# incubator.net
KiCad netlist of a schematic drawn in EAGLE
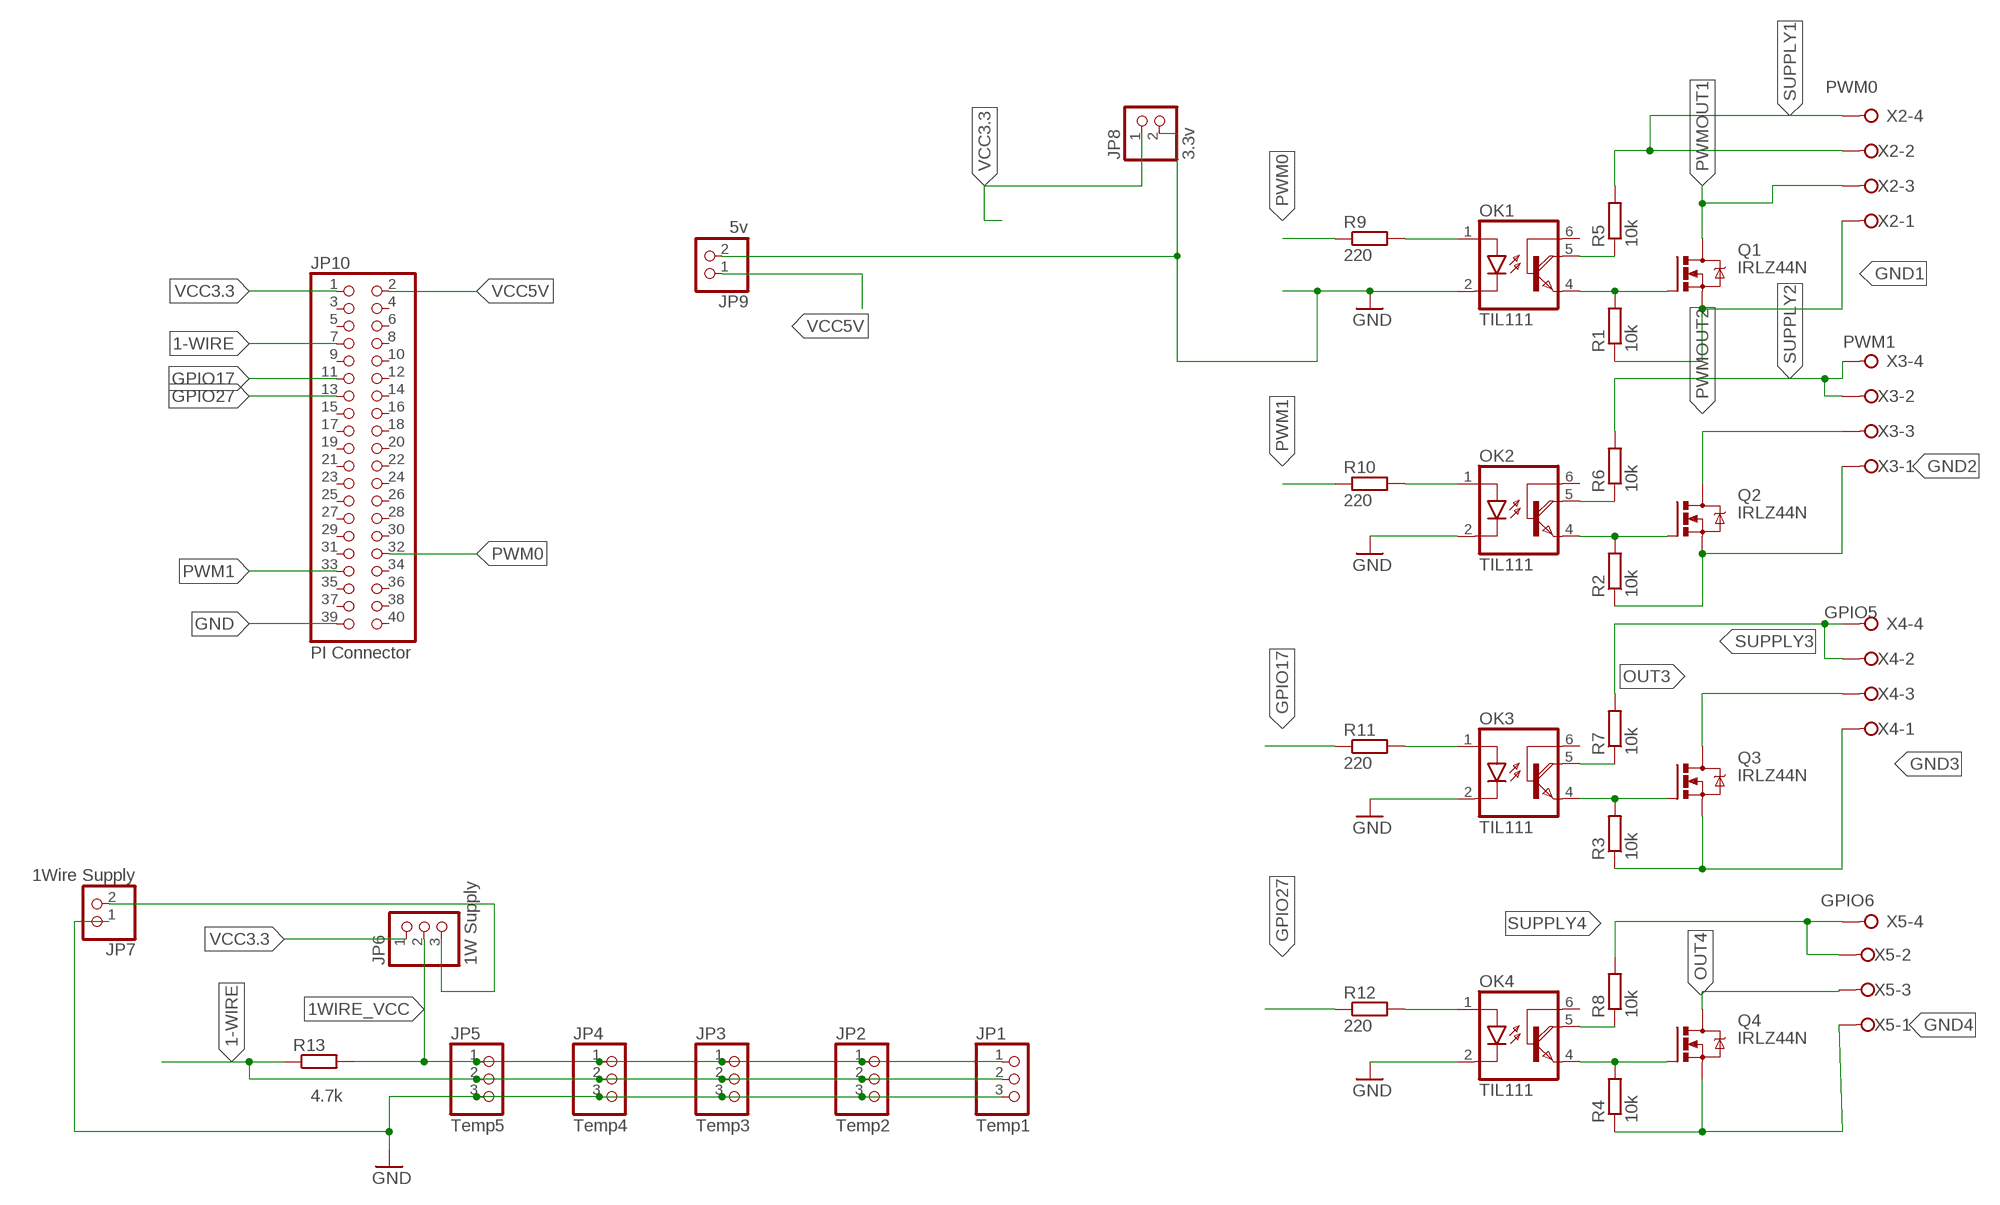
[diagram p0: schematic, sheet 1]

(export (version "E")
  (design (tool "Eeschema 10.0.6"))
  (components
    (comp (ref "JP1")
      (value "Temp1")
      (footprint "eagle-import:1X03")
      (libsource (lib "eagle-import") (part "PINHD-1X3"))
    )
    (comp (ref "JP2")
      (value "Temp2")
      (footprint "eagle-import:1X03")
      (libsource (lib "eagle-import") (part "PINHD-1X3"))
    )
    (comp (ref "JP3")
      (value "Temp3")
      (footprint "eagle-import:1X03")
      (libsource (lib "eagle-import") (part "PINHD-1X3"))
    )
    (comp (ref "JP4")
      (value "Temp4")
      (footprint "eagle-import:1X03")
      (libsource (lib "eagle-import") (part "PINHD-1X3"))
    )
    (comp (ref "JP5")
      (value "Temp5")
      (footprint "eagle-import:1X03")
      (libsource (lib "eagle-import") (part "PINHD-1X3"))
    )
    (comp (ref "JP6")
      (value "1W Supply")
      (footprint "eagle-import:1X03")
      (libsource (lib "eagle-import") (part "PINHD-1X3"))
    )
    (comp (ref "JP7")
      (value "1Wire Supply")
      (footprint "eagle-import:1X02")
      (libsource (lib "eagle-import") (part "PINHD-1X2"))
    )
    (comp (ref "JP8")
      (value "3.3v")
      (footprint "eagle-import:1X02")
      (libsource (lib "eagle-import") (part "PINHD-1X2"))
    )
    (comp (ref "JP9")
      (value "5v")
      (footprint "eagle-import:1X02")
      (libsource (lib "eagle-import") (part "PINHD-1X2"))
    )
    (comp (ref "JP10")
      (value "PI Connector")
      (footprint "eagle-import:2X20")
      (libsource (lib "eagle-import") (part "PINHD-2X20"))
    )
    (comp (ref "OK1")
      (value "TIL111")
      (footprint "eagle-import:DIL06")
      (fields (field (name "MF") "VISHAY/TELEFUNKEN") (field (name "MPN") "4N33"))
      (libsource (lib "eagle-import") (part "4N33"))
    )
    (comp (ref "OK2")
      (value "TIL111")
      (footprint "eagle-import:DIL06")
      (fields (field (name "MF") "VISHAY/TELEFUNKEN") (field (name "MPN") "4N33"))
      (libsource (lib "eagle-import") (part "4N33"))
    )
    (comp (ref "OK3")
      (value "TIL111")
      (footprint "eagle-import:DIL06")
      (fields (field (name "MF") "VISHAY/TELEFUNKEN") (field (name "MPN") "4N33"))
      (libsource (lib "eagle-import") (part "4N33"))
    )
    (comp (ref "OK4")
      (value "TIL111")
      (footprint "eagle-import:DIL06")
      (fields (field (name "MF") "VISHAY/TELEFUNKEN") (field (name "MPN") "4N33"))
      (libsource (lib "eagle-import") (part "4N33"))
    )
    (comp (ref "Q1")
      (value "IRLZ44N")
      (footprint "eagle-import:TO220BH")
      (libsource (lib "eagle-import") (part "IRLZ44Z"))
    )
    (comp (ref "Q2")
      (value "IRLZ44N")
      (footprint "eagle-import:TO220BH")
      (libsource (lib "eagle-import") (part "IRLZ44Z"))
    )
    (comp (ref "Q3")
      (value "IRLZ44N")
      (footprint "eagle-import:TO220BH")
      (libsource (lib "eagle-import") (part "IRLZ44Z"))
    )
    (comp (ref "Q4")
      (value "IRLZ44N")
      (footprint "eagle-import:TO220BH")
      (libsource (lib "eagle-import") (part "IRLZ44Z"))
    )
    (comp (ref "R1")
      (value "10k")
      (footprint "eagle-import:0207_7")
      (libsource (lib "eagle-import") (part "R-EU_0207/7"))
    )
    (comp (ref "R2")
      (value "10k")
      (footprint "eagle-import:0207_7")
      (libsource (lib "eagle-import") (part "R-EU_0207/7"))
    )
    (comp (ref "R3")
      (value "10k")
      (footprint "eagle-import:0207_7")
      (libsource (lib "eagle-import") (part "R-EU_0207/7"))
    )
    (comp (ref "R4")
      (value "10k")
      (footprint "eagle-import:0207_7")
      (libsource (lib "eagle-import") (part "R-EU_0207/7"))
    )
    (comp (ref "R5")
      (value "10k")
      (footprint "eagle-import:0207_7")
      (libsource (lib "eagle-import") (part "R-EU_0207/7"))
    )
    (comp (ref "R6")
      (value "10k")
      (footprint "eagle-import:0207_7")
      (libsource (lib "eagle-import") (part "R-EU_0207/7"))
    )
    (comp (ref "R7")
      (value "10k")
      (footprint "eagle-import:0207_7")
      (libsource (lib "eagle-import") (part "R-EU_0207/7"))
    )
    (comp (ref "R8")
      (value "10k")
      (footprint "eagle-import:0207_7")
      (libsource (lib "eagle-import") (part "R-EU_0207/7"))
    )
    (comp (ref "R9")
      (value "220")
      (footprint "eagle-import:0207_7")
      (libsource (lib "eagle-import") (part "R-EU_0207/7"))
    )
    (comp (ref "R10")
      (value "220")
      (footprint "eagle-import:0207_7")
      (libsource (lib "eagle-import") (part "R-EU_0207/7"))
    )
    (comp (ref "R11")
      (value "220")
      (footprint "eagle-import:0207_7")
      (libsource (lib "eagle-import") (part "R-EU_0207/7"))
    )
    (comp (ref "R12")
      (value "220")
      (footprint "eagle-import:0207_7")
      (libsource (lib "eagle-import") (part "R-EU_0207/7"))
    )
    (comp (ref "R13")
      (value "4.7k")
      (footprint "eagle-import:0207_7")
      (libsource (lib "eagle-import") (part "R-EU_0207/7"))
    )
    (comp (ref "X2")
      (value "PWM0")
      (footprint "eagle-import:W237-4P")
      (libsource (lib "eagle-import") (part "W237-04P"))
    )
    (comp (ref "X3")
      (value "PWM1")
      (footprint "eagle-import:W237-4P")
      (libsource (lib "eagle-import") (part "W237-04P"))
    )
    (comp (ref "X4")
      (value "GPIO5")
      (footprint "eagle-import:W237-4P")
      (libsource (lib "eagle-import") (part "W237-04P"))
    )
    (comp (ref "X5")
      (value "GPIO6")
      (footprint "eagle-import:W237-4P")
      (libsource (lib "eagle-import") (part "W237-04P"))
    )
  )
  (nets
    (net (code "1") (name "1-WIRE") (class "Default")
      (node (ref "JP1") (pin "2") (pinfunction "2_2") (pintype "passive"))
      (node (ref "JP10") (pin "7") (pinfunction "7_7") (pintype "passive"))
      (node (ref "JP2") (pin "2") (pinfunction "2_2") (pintype "passive"))
      (node (ref "JP3") (pin "2") (pinfunction "2_2") (pintype "passive"))
      (node (ref "JP4") (pin "2") (pinfunction "2_2") (pintype "passive"))
      (node (ref "JP5") (pin "2") (pinfunction "2_2") (pintype "passive"))
      (node (ref "R13") (pin "1") (pinfunction "1_1") (pintype "passive"))
    )
    (net (code "2") (name "1WIRE_VCC") (class "Default")
      (node (ref "JP1") (pin "1") (pinfunction "1_1") (pintype "passive"))
      (node (ref "JP2") (pin "1") (pinfunction "1_1") (pintype "passive"))
      (node (ref "JP3") (pin "1") (pinfunction "1_1") (pintype "passive"))
      (node (ref "JP4") (pin "1") (pinfunction "1_1") (pintype "passive"))
      (node (ref "JP5") (pin "1") (pinfunction "1_1") (pintype "passive"))
      (node (ref "JP6") (pin "2") (pinfunction "2_2") (pintype "passive"))
      (node (ref "R13") (pin "2") (pinfunction "2_2") (pintype "passive"))
    )
    (net (code "3") (name "GND") (class "Default")
      (node (ref "JP1") (pin "3") (pinfunction "3_3") (pintype "passive"))
      (node (ref "JP10") (pin "39") (pinfunction "39_39") (pintype "passive"))
      (node (ref "JP2") (pin "3") (pinfunction "3_3") (pintype "passive"))
      (node (ref "JP3") (pin "3") (pinfunction "3_3") (pintype "passive"))
      (node (ref "JP4") (pin "3") (pinfunction "3_3") (pintype "passive"))
      (node (ref "JP5") (pin "3") (pinfunction "3_3") (pintype "passive"))
      (node (ref "JP7") (pin "1") (pinfunction "1_1") (pintype "passive"))
      (node (ref "JP8") (pin "2") (pinfunction "2_2") (pintype "passive"))
      (node (ref "JP9") (pin "2") (pinfunction "2_2") (pintype "passive"))
      (node (ref "OK1") (pin "2") (pinfunction "C_2") (pintype "passive"))
      (node (ref "OK2") (pin "2") (pinfunction "C_2") (pintype "passive"))
      (node (ref "OK3") (pin "2") (pinfunction "C_2") (pintype "passive"))
      (node (ref "OK4") (pin "2") (pinfunction "C_2") (pintype "passive"))
    )
    (net (code "4") (name "GND1") (class "Default")
      (node (ref "Q1") (pin "S") (pinfunction "S_S") (pintype "passive"))
      (node (ref "R1") (pin "1") (pinfunction "1_1") (pintype "passive"))
      (node (ref "X2") (pin "1") (pinfunction "KL_1") (pintype "passive"))
    )
    (net (code "5") (name "GND2") (class "Default")
      (node (ref "Q2") (pin "S") (pinfunction "S_S") (pintype "passive"))
      (node (ref "R2") (pin "1") (pinfunction "1_1") (pintype "passive"))
      (node (ref "X3") (pin "1") (pinfunction "KL_1") (pintype "passive"))
    )
    (net (code "6") (name "GND3") (class "Default")
      (node (ref "Q3") (pin "S") (pinfunction "S_S") (pintype "passive"))
      (node (ref "R3") (pin "1") (pinfunction "1_1") (pintype "passive"))
      (node (ref "X4") (pin "1") (pinfunction "KL_1") (pintype "passive"))
    )
    (net (code "7") (name "GND4") (class "Default")
      (node (ref "Q4") (pin "S") (pinfunction "S_S") (pintype "passive"))
      (node (ref "R4") (pin "1") (pinfunction "1_1") (pintype "passive"))
      (node (ref "X5") (pin "1") (pinfunction "KL_1") (pintype "passive"))
    )
    (net (code "8") (name "GPIO17") (class "Default")
      (node (ref "JP10") (pin "11") (pinfunction "11_11") (pintype "passive"))
      (node (ref "R11") (pin "1") (pinfunction "1_1") (pintype "passive"))
    )
    (net (code "9") (name "GPIO27") (class "Default")
      (node (ref "JP10") (pin "13") (pinfunction "13_13") (pintype "passive"))
      (node (ref "R12") (pin "1") (pinfunction "1_1") (pintype "passive"))
    )
    (net (code "10") (name "Net-(JP6-Pad3)") (class "Default")
      (node (ref "JP6") (pin "3") (pinfunction "3_3") (pintype "passive"))
      (node (ref "JP7") (pin "2") (pinfunction "2_2") (pintype "passive"))
    )
    (net (code "11") (name "Net-(OK1-A)") (class "Default")
      (node (ref "OK1") (pin "1") (pinfunction "A_1") (pintype "passive"))
      (node (ref "R9") (pin "2") (pinfunction "2_2") (pintype "passive"))
    )
    (net (code "12") (name "Net-(OK1-COL)") (class "Default")
      (node (ref "OK1") (pin "5") (pinfunction "COL_5") (pintype "passive"))
      (node (ref "R5") (pin "1") (pinfunction "1_1") (pintype "passive"))
    )
    (net (code "13") (name "Net-(OK1-E)") (class "Default")
      (node (ref "OK1") (pin "4") (pinfunction "E_4") (pintype "passive"))
      (node (ref "Q1") (pin "G") (pinfunction "G_G") (pintype "passive"))
      (node (ref "R1") (pin "2") (pinfunction "2_2") (pintype "passive"))
    )
    (net (code "14") (name "Net-(OK2-A)") (class "Default")
      (node (ref "OK2") (pin "1") (pinfunction "A_1") (pintype "passive"))
      (node (ref "R10") (pin "2") (pinfunction "2_2") (pintype "passive"))
    )
    (net (code "15") (name "Net-(OK2-COL)") (class "Default")
      (node (ref "OK2") (pin "5") (pinfunction "COL_5") (pintype "passive"))
      (node (ref "R6") (pin "1") (pinfunction "1_1") (pintype "passive"))
    )
    (net (code "16") (name "Net-(OK2-E)") (class "Default")
      (node (ref "OK2") (pin "4") (pinfunction "E_4") (pintype "passive"))
      (node (ref "Q2") (pin "G") (pinfunction "G_G") (pintype "passive"))
      (node (ref "R2") (pin "2") (pinfunction "2_2") (pintype "passive"))
    )
    (net (code "17") (name "Net-(OK3-A)") (class "Default")
      (node (ref "OK3") (pin "1") (pinfunction "A_1") (pintype "passive"))
      (node (ref "R11") (pin "2") (pinfunction "2_2") (pintype "passive"))
    )
    (net (code "18") (name "Net-(OK3-COL)") (class "Default")
      (node (ref "OK3") (pin "5") (pinfunction "COL_5") (pintype "passive"))
      (node (ref "R7") (pin "1") (pinfunction "1_1") (pintype "passive"))
    )
    (net (code "19") (name "Net-(OK3-E)") (class "Default")
      (node (ref "OK3") (pin "4") (pinfunction "E_4") (pintype "passive"))
      (node (ref "Q3") (pin "G") (pinfunction "G_G") (pintype "passive"))
      (node (ref "R3") (pin "2") (pinfunction "2_2") (pintype "passive"))
    )
    (net (code "20") (name "Net-(OK4-A)") (class "Default")
      (node (ref "OK4") (pin "1") (pinfunction "A_1") (pintype "passive"))
      (node (ref "R12") (pin "2") (pinfunction "2_2") (pintype "passive"))
    )
    (net (code "21") (name "Net-(OK4-COL)") (class "Default")
      (node (ref "OK4") (pin "5") (pinfunction "COL_5") (pintype "passive"))
      (node (ref "R8") (pin "1") (pinfunction "1_1") (pintype "passive"))
    )
    (net (code "22") (name "Net-(OK4-E)") (class "Default")
      (node (ref "OK4") (pin "4") (pinfunction "E_4") (pintype "passive"))
      (node (ref "Q4") (pin "G") (pinfunction "G_G") (pintype "passive"))
      (node (ref "R4") (pin "2") (pinfunction "2_2") (pintype "passive"))
    )
    (net (code "23") (name "OUT3") (class "Default")
      (node (ref "Q3") (pin "D") (pinfunction "D_D") (pintype "passive"))
      (node (ref "X4") (pin "3") (pinfunction "KL_3") (pintype "passive"))
    )
    (net (code "24") (name "OUT4") (class "Default")
      (node (ref "Q4") (pin "D") (pinfunction "D_D") (pintype "passive"))
      (node (ref "X5") (pin "3") (pinfunction "KL_3") (pintype "passive"))
    )
    (net (code "25") (name "PWM0") (class "Default")
      (node (ref "JP10") (pin "32") (pinfunction "32_32") (pintype "passive"))
      (node (ref "R9") (pin "1") (pinfunction "1_1") (pintype "passive"))
    )
    (net (code "26") (name "PWM1") (class "Default")
      (node (ref "JP10") (pin "33") (pinfunction "33_33") (pintype "passive"))
      (node (ref "R10") (pin "1") (pinfunction "1_1") (pintype "passive"))
    )
    (net (code "27") (name "PWMOUT1") (class "Default")
      (node (ref "Q1") (pin "D") (pinfunction "D_D") (pintype "passive"))
      (node (ref "X2") (pin "3") (pinfunction "KL_3") (pintype "passive"))
    )
    (net (code "28") (name "PWMOUT2") (class "Default")
      (node (ref "Q2") (pin "D") (pinfunction "D_D") (pintype "passive"))
      (node (ref "X3") (pin "3") (pinfunction "KL_3") (pintype "passive"))
    )
    (net (code "29") (name "SUPPLY1") (class "Default")
      (node (ref "R5") (pin "2") (pinfunction "2_2") (pintype "passive"))
      (node (ref "X2") (pin "2") (pinfunction "KL_2") (pintype "passive"))
      (node (ref "X2") (pin "4") (pinfunction "KL_4") (pintype "passive"))
    )
    (net (code "30") (name "SUPPLY2") (class "Default")
      (node (ref "R6") (pin "2") (pinfunction "2_2") (pintype "passive"))
      (node (ref "X3") (pin "2") (pinfunction "KL_2") (pintype "passive"))
      (node (ref "X3") (pin "4") (pinfunction "KL_4") (pintype "passive"))
    )
    (net (code "31") (name "SUPPLY3") (class "Default")
      (node (ref "R7") (pin "2") (pinfunction "2_2") (pintype "passive"))
      (node (ref "X4") (pin "2") (pinfunction "KL_2") (pintype "passive"))
      (node (ref "X4") (pin "4") (pinfunction "KL_4") (pintype "passive"))
    )
    (net (code "32") (name "SUPPLY4") (class "Default")
      (node (ref "R8") (pin "2") (pinfunction "2_2") (pintype "passive"))
      (node (ref "X5") (pin "2") (pinfunction "KL_2") (pintype "passive"))
      (node (ref "X5") (pin "4") (pinfunction "KL_4") (pintype "passive"))
    )
    (net (code "33") (name "VCC3.3") (class "Default")
      (node (ref "JP10") (pin "1") (pinfunction "1_1") (pintype "passive"))
      (node (ref "JP6") (pin "1") (pinfunction "1_1") (pintype "passive"))
      (node (ref "JP8") (pin "1") (pinfunction "1_1") (pintype "passive"))
    )
    (net (code "34") (name "VCC5V") (class "Default")
      (node (ref "JP10") (pin "2") (pinfunction "2_2") (pintype "passive"))
      (node (ref "JP9") (pin "1") (pinfunction "1_1") (pintype "passive"))
    )
    (net (code "35") (name "unconnected-(JP10-Pad3)") (class "Default")
      (node (ref "JP10") (pin "3") (pinfunction "3_3") (pintype "passive"))
    )
    (net (code "36") (name "unconnected-(JP10-Pad4)") (class "Default")
      (node (ref "JP10") (pin "4") (pinfunction "4_4") (pintype "passive"))
    )
    (net (code "37") (name "unconnected-(JP10-Pad5)") (class "Default")
      (node (ref "JP10") (pin "5") (pinfunction "5_5") (pintype "passive"))
    )
    (net (code "38") (name "unconnected-(JP10-Pad6)") (class "Default")
      (node (ref "JP10") (pin "6") (pinfunction "6_6") (pintype "passive"))
    )
    (net (code "39") (name "unconnected-(JP10-Pad8)") (class "Default")
      (node (ref "JP10") (pin "8") (pinfunction "8_8") (pintype "passive"))
    )
    (net (code "40") (name "unconnected-(JP10-Pad9)") (class "Default")
      (node (ref "JP10") (pin "9") (pinfunction "9_9") (pintype "passive"))
    )
    (net (code "41") (name "unconnected-(JP10-Pad10)") (class "Default")
      (node (ref "JP10") (pin "10") (pinfunction "10_10") (pintype "passive"))
    )
    (net (code "42") (name "unconnected-(JP10-Pad12)") (class "Default")
      (node (ref "JP10") (pin "12") (pinfunction "12_12") (pintype "passive"))
    )
    (net (code "43") (name "unconnected-(JP10-Pad14)") (class "Default")
      (node (ref "JP10") (pin "14") (pinfunction "14_14") (pintype "passive"))
    )
    (net (code "44") (name "unconnected-(JP10-Pad15)") (class "Default")
      (node (ref "JP10") (pin "15") (pinfunction "15_15") (pintype "passive"))
    )
    (net (code "45") (name "unconnected-(JP10-Pad16)") (class "Default")
      (node (ref "JP10") (pin "16") (pinfunction "16_16") (pintype "passive"))
    )
    (net (code "46") (name "unconnected-(JP10-Pad17)") (class "Default")
      (node (ref "JP10") (pin "17") (pinfunction "17_17") (pintype "passive"))
    )
    (net (code "47") (name "unconnected-(JP10-Pad18)") (class "Default")
      (node (ref "JP10") (pin "18") (pinfunction "18_18") (pintype "passive"))
    )
    (net (code "48") (name "unconnected-(JP10-Pad19)") (class "Default")
      (node (ref "JP10") (pin "19") (pinfunction "19_19") (pintype "passive"))
    )
    (net (code "49") (name "unconnected-(JP10-Pad20)") (class "Default")
      (node (ref "JP10") (pin "20") (pinfunction "20_20") (pintype "passive"))
    )
    (net (code "50") (name "unconnected-(JP10-Pad21)") (class "Default")
      (node (ref "JP10") (pin "21") (pinfunction "21_21") (pintype "passive"))
    )
    (net (code "51") (name "unconnected-(JP10-Pad22)") (class "Default")
      (node (ref "JP10") (pin "22") (pinfunction "22_22") (pintype "passive"))
    )
    (net (code "52") (name "unconnected-(JP10-Pad23)") (class "Default")
      (node (ref "JP10") (pin "23") (pinfunction "23_23") (pintype "passive"))
    )
    (net (code "53") (name "unconnected-(JP10-Pad24)") (class "Default")
      (node (ref "JP10") (pin "24") (pinfunction "24_24") (pintype "passive"))
    )
    (net (code "54") (name "unconnected-(JP10-Pad25)") (class "Default")
      (node (ref "JP10") (pin "25") (pinfunction "25_25") (pintype "passive"))
    )
    (net (code "55") (name "unconnected-(JP10-Pad26)") (class "Default")
      (node (ref "JP10") (pin "26") (pinfunction "26_26") (pintype "passive"))
    )
    (net (code "56") (name "unconnected-(JP10-Pad27)") (class "Default")
      (node (ref "JP10") (pin "27") (pinfunction "27_27") (pintype "passive"))
    )
    (net (code "57") (name "unconnected-(JP10-Pad28)") (class "Default")
      (node (ref "JP10") (pin "28") (pinfunction "28_28") (pintype "passive"))
    )
    (net (code "58") (name "unconnected-(JP10-Pad29)") (class "Default")
      (node (ref "JP10") (pin "29") (pinfunction "29_29") (pintype "passive"))
    )
    (net (code "59") (name "unconnected-(JP10-Pad30)") (class "Default")
      (node (ref "JP10") (pin "30") (pinfunction "30_30") (pintype "passive"))
    )
    (net (code "60") (name "unconnected-(JP10-Pad31)") (class "Default")
      (node (ref "JP10") (pin "31") (pinfunction "31_31") (pintype "passive"))
    )
    (net (code "61") (name "unconnected-(JP10-Pad34)") (class "Default")
      (node (ref "JP10") (pin "34") (pinfunction "34_34") (pintype "passive"))
    )
    (net (code "62") (name "unconnected-(JP10-Pad35)") (class "Default")
      (node (ref "JP10") (pin "35") (pinfunction "35_35") (pintype "passive"))
    )
    (net (code "63") (name "unconnected-(JP10-Pad36)") (class "Default")
      (node (ref "JP10") (pin "36") (pinfunction "36_36") (pintype "passive"))
    )
    (net (code "64") (name "unconnected-(JP10-Pad37)") (class "Default")
      (node (ref "JP10") (pin "37") (pinfunction "37_37") (pintype "passive"))
    )
    (net (code "65") (name "unconnected-(JP10-Pad38)") (class "Default")
      (node (ref "JP10") (pin "38") (pinfunction "38_38") (pintype "passive"))
    )
    (net (code "66") (name "unconnected-(JP10-Pad40)") (class "Default")
      (node (ref "JP10") (pin "40") (pinfunction "40_40") (pintype "passive"))
    )
    (net (code "67") (name "unconnected-(OK1-B-Pad6)") (class "Default")
      (node (ref "OK1") (pin "6") (pinfunction "B_6") (pintype "passive"))
    )
    (net (code "68") (name "unconnected-(OK2-B-Pad6)") (class "Default")
      (node (ref "OK2") (pin "6") (pinfunction "B_6") (pintype "passive"))
    )
    (net (code "69") (name "unconnected-(OK3-B-Pad6)") (class "Default")
      (node (ref "OK3") (pin "6") (pinfunction "B_6") (pintype "passive"))
    )
    (net (code "70") (name "unconnected-(OK4-B-Pad6)") (class "Default")
      (node (ref "OK4") (pin "6") (pinfunction "B_6") (pintype "passive"))
    )
  )
)
